# Power_-_3V3.net
KiCad netlist of a schematic drawn in Altium Designer
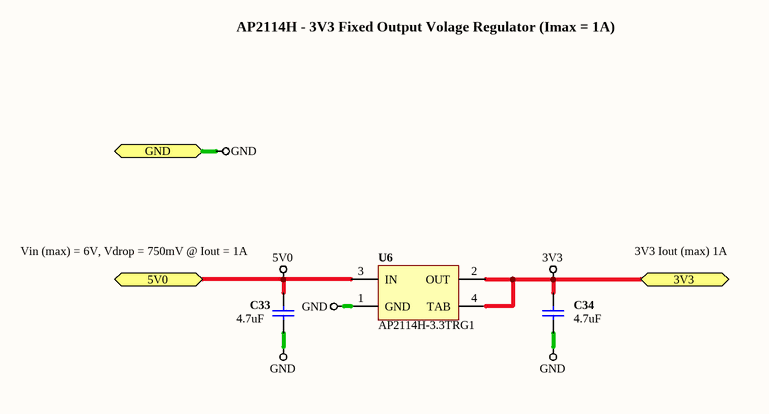
[diagram p0: Power - 3V3.SchDoc]

(export (version "E")
  (design (tool "Eeschema 10.0.6"))
  (components
    (comp (ref "C33")
      (value "4.7uF")
      (footprint "CAPC0603(1608)55_L")
      (fields (field (name "TOLERANCE") "±10%") (field (name "Comment") "CAP 4.7uF 10V 0603(1608)"))
      (libsource (lib "Component_Database") (part "CAP_NP"))
    )
    (comp (ref "C34")
      (value "4.7uF")
      (footprint "CAPC0603(1608)55_L")
      (fields (field (name "TOLERANCE") "±10%") (field (name "Comment") "CAP 4.7uF 10V 0603(1608)"))
      (libsource (lib "Component_Database") (part "CAP_NP"))
    )
    (comp (ref "U6")
      (value "AP2114H-3.3TRG1")
      (footprint "SOT230P700X180-4L")
      (description "AP2114, 1A Low Dropout Positive Fixed 3V3 Regulator")
      (libsource (lib "AP2114H-3.3TRG1") (part "AP2114H-3.3TRG1"))
    )
  )
  (nets
    (net (code "1") (name "3V3") (class "Default")
      (node (ref "C34") (pin "1") (pinfunction "1_1") (pintype "passive"))
      (node (ref "U6") (pin "2") (pinfunction "OUT_2") (pintype "power_in"))
      (node (ref "U6") (pin "4") (pinfunction "TAB_4") (pintype "power_in"))
    )
    (net (code "2") (name "5V0") (class "Default")
      (node (ref "C33") (pin "1") (pinfunction "1_1") (pintype "passive"))
      (node (ref "U6") (pin "3") (pinfunction "IN_3") (pintype "power_in"))
    )
    (net (code "3") (name "GND") (class "Default")
      (node (ref "C33") (pin "2") (pinfunction "2_2") (pintype "passive"))
      (node (ref "C34") (pin "2") (pinfunction "2_2") (pintype "passive"))
      (node (ref "U6") (pin "1") (pinfunction "GND_1") (pintype "power_in"))
    )
  )
)
